# v1.net
KiCad netlist of a schematic drawn in EAGLE
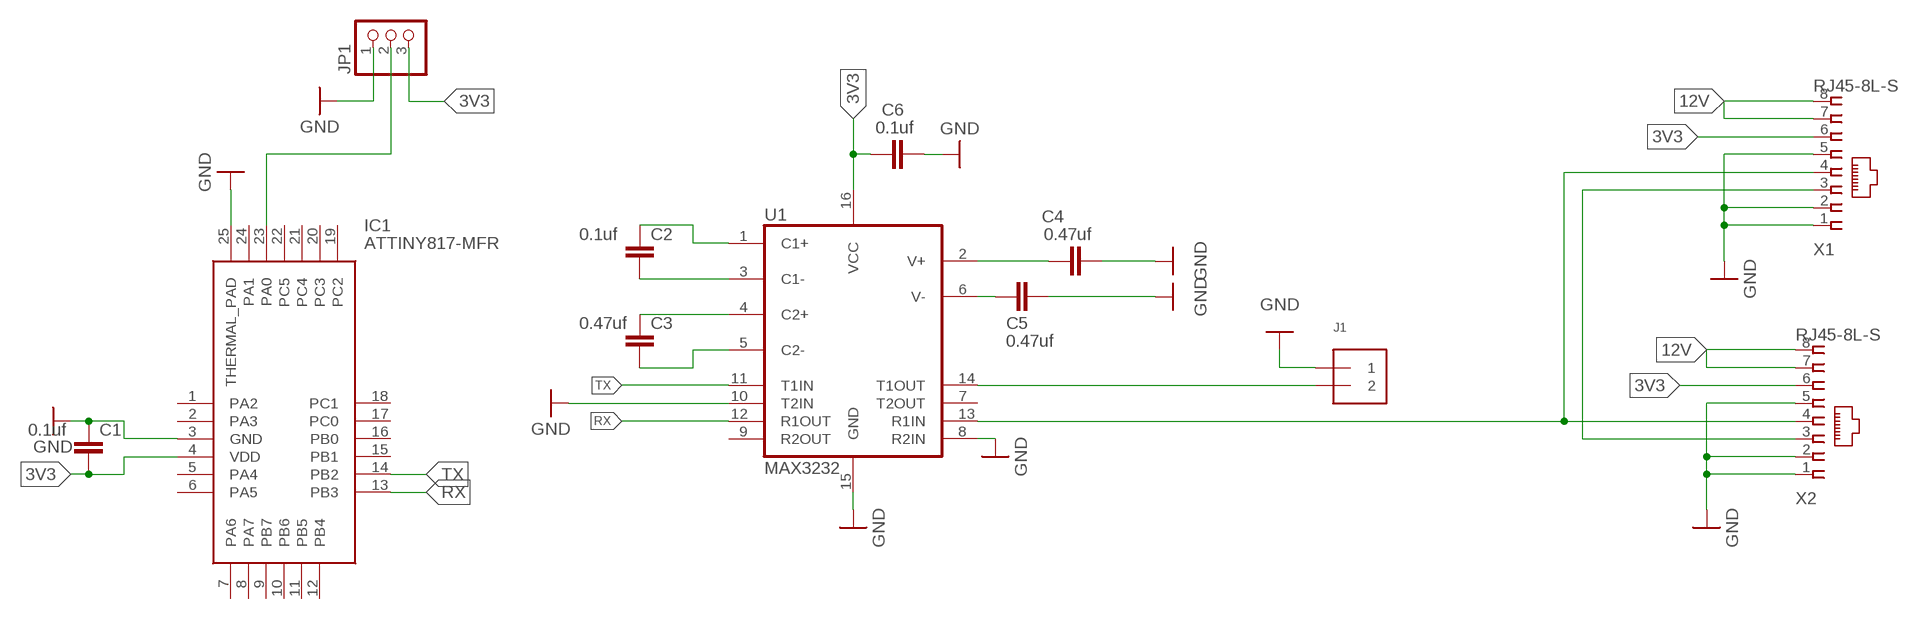
[diagram p0: schematic, sheet 1]

(export (version "E")
  (design (tool "Eeschema 10.0.6"))
  (components
    (comp (ref "C1")
      (value "0.1uf")
      (footprint "eagle-import:C0805")
      (libsource (lib "eagle-import") (part "C-EUC0805"))
    )
    (comp (ref "C2")
      (value "0.1uf")
      (footprint "eagle-import:C0805")
      (libsource (lib "eagle-import") (part "C-EUC0805"))
    )
    (comp (ref "C3")
      (value "0.47uf")
      (footprint "eagle-import:C0805")
      (libsource (lib "eagle-import") (part "C-EUC0805"))
    )
    (comp (ref "C4")
      (value "0.47uf")
      (footprint "eagle-import:C0805")
      (libsource (lib "eagle-import") (part "C-EUC0805"))
    )
    (comp (ref "C5")
      (value "0.47uf")
      (footprint "eagle-import:C0805")
      (libsource (lib "eagle-import") (part "C-EUC0805"))
    )
    (comp (ref "C6")
      (value "0.1uf")
      (footprint "eagle-import:C0805")
      (libsource (lib "eagle-import") (part "C-EUC0805"))
    )
    (comp (ref "IC1")
      (value "ATTINY817-MFR")
      (footprint "eagle-import:QFN50P400X400X90-25N")
      (fields
        (field (name "MOUSER_PART_NUMBER") "579-ATTINY817-MFR")
        (field (name "RS_PART_NUMBER") "1682807P")
      )
      (libsource (lib "eagle-import") (part "ATTINY817-MFR"))
    )
    (comp (ref "J1")
      (value "TERMBLOCK_1X2")
      (footprint "eagle-import:TERMBLOCK_1X2-3.5MM")
      (libsource (lib "eagle-import") (part "TERMBLOCK_1X2"))
    )
    (comp (ref "JP1")
      (value "PINHD-1X3")
      (footprint "eagle-import:1X03")
      (libsource (lib "eagle-import") (part "PINHD-1X3"))
    )
    (comp (ref "U1")
      (value "MAX3232")
      (footprint "eagle-import:SO16")
      (libsource (lib "eagle-import") (part "MAX2323SOIC16"))
    )
    (comp (ref "X1")
      (value "RJ45-8L-S")
      (footprint "eagle-import:RJ45-NO-SHIELD")
      (fields (field (name "MF") "TYCO ELECTRONICS"))
      (libsource (lib "eagle-import") (part "RJ45-8L-S"))
    )
    (comp (ref "X2")
      (value "RJ45-8L-S")
      (footprint "eagle-import:RJ45-NO-SHIELD")
      (fields (field (name "MF") "TYCO ELECTRONICS"))
      (libsource (lib "eagle-import") (part "RJ45-8L-S"))
    )
  )
  (nets
    (net (code "1") (name "3V3") (class "Default")
      (node (ref "C1") (pin "2") (pinfunction "2_2") (pintype "passive"))
      (node (ref "C6") (pin "2") (pinfunction "2_2") (pintype "passive"))
      (node (ref "IC1") (pin "4") (pinfunction "VDD_4") (pintype "bidirectional"))
      (node (ref "JP1") (pin "3") (pinfunction "3_3") (pintype "passive"))
      (node (ref "U1") (pin "16") (pinfunction "VCC_16") (pintype "bidirectional"))
      (node (ref "X1") (pin "6") (pinfunction "6_6") (pintype "passive"))
      (node (ref "X2") (pin "6") (pinfunction "6_6") (pintype "passive"))
    )
    (net (code "2") (name "12V") (class "Default")
      (node (ref "X1") (pin "7") (pinfunction "7_7") (pintype "passive"))
      (node (ref "X1") (pin "8") (pinfunction "8_8") (pintype "passive"))
      (node (ref "X2") (pin "7") (pinfunction "7_7") (pintype "passive"))
      (node (ref "X2") (pin "8") (pinfunction "8_8") (pintype "passive"))
    )
    (net (code "3") (name "GND") (class "Default")
      (node (ref "C1") (pin "1") (pinfunction "1_1") (pintype "passive"))
      (node (ref "C4") (pin "1") (pinfunction "1_1") (pintype "passive"))
      (node (ref "C5") (pin "1") (pinfunction "1_1") (pintype "passive"))
      (node (ref "C6") (pin "1") (pinfunction "1_1") (pintype "passive"))
      (node (ref "IC1") (pin "25") (pinfunction "THERMAL_PAD_25") (pintype "bidirectional"))
      (node (ref "IC1") (pin "3") (pinfunction "GND_3") (pintype "bidirectional"))
      (node (ref "J1") (pin "1") (pinfunction "1_1") (pintype "passive"))
      (node (ref "JP1") (pin "1") (pinfunction "1_1") (pintype "passive"))
      (node (ref "U1") (pin "10") (pinfunction "T2IN_10") (pintype "input"))
      (node (ref "U1") (pin "15") (pinfunction "GND_15") (pintype "bidirectional"))
      (node (ref "U1") (pin "8") (pinfunction "R2IN_8") (pintype "input"))
      (node (ref "X1") (pin "1") (pinfunction "1_1") (pintype "passive"))
      (node (ref "X1") (pin "2") (pinfunction "2_2") (pintype "passive"))
      (node (ref "X1") (pin "5") (pinfunction "5_5") (pintype "passive"))
      (node (ref "X2") (pin "1") (pinfunction "1_1") (pintype "passive"))
      (node (ref "X2") (pin "2") (pinfunction "2_2") (pintype "passive"))
      (node (ref "X2") (pin "5") (pinfunction "5_5") (pintype "passive"))
    )
    (net (code "4") (name "Net-(IC1-PA0)") (class "Default")
      (node (ref "IC1") (pin "23") (pinfunction "PA0_23") (pintype "bidirectional"))
      (node (ref "JP1") (pin "2") (pinfunction "2_2") (pintype "passive"))
    )
    (net (code "5") (name "Net-(U1-C1+)") (class "Default")
      (node (ref "C2") (pin "1") (pinfunction "1_1") (pintype "passive"))
      (node (ref "U1") (pin "1") (pinfunction "C1+_1") (pintype "bidirectional"))
    )
    (net (code "6") (name "Net-(U1-C1-)") (class "Default")
      (node (ref "C2") (pin "2") (pinfunction "2_2") (pintype "passive"))
      (node (ref "U1") (pin "3") (pinfunction "C1-_3") (pintype "bidirectional"))
    )
    (net (code "7") (name "Net-(U1-C2+)") (class "Default")
      (node (ref "C3") (pin "1") (pinfunction "1_1") (pintype "passive"))
      (node (ref "U1") (pin "4") (pinfunction "C2+_4") (pintype "bidirectional"))
    )
    (net (code "8") (name "Net-(U1-C2-)") (class "Default")
      (node (ref "C3") (pin "2") (pinfunction "2_2") (pintype "passive"))
      (node (ref "U1") (pin "5") (pinfunction "C2-_5") (pintype "bidirectional"))
    )
    (net (code "9") (name "Net-(U1-R1IN)") (class "Default")
      (node (ref "U1") (pin "13") (pinfunction "R1IN_13") (pintype "input"))
      (node (ref "X1") (pin "4") (pinfunction "4_4") (pintype "passive"))
      (node (ref "X2") (pin "4") (pinfunction "4_4") (pintype "passive"))
    )
    (net (code "10") (name "Net-(U1-T1OUT)") (class "Default")
      (node (ref "J1") (pin "2") (pinfunction "2_2") (pintype "passive"))
      (node (ref "U1") (pin "14") (pinfunction "T1OUT_14") (pintype "output"))
    )
    (net (code "11") (name "Net-(U1-V+)") (class "Default")
      (node (ref "C4") (pin "2") (pinfunction "2_2") (pintype "passive"))
      (node (ref "U1") (pin "2") (pinfunction "V+_2") (pintype "bidirectional"))
    )
    (net (code "12") (name "Net-(U1-V-)") (class "Default")
      (node (ref "C5") (pin "2") (pinfunction "2_2") (pintype "passive"))
      (node (ref "U1") (pin "6") (pinfunction "V-_6") (pintype "bidirectional"))
    )
    (net (code "13") (name "Net-(X1-Pad3)") (class "Default")
      (node (ref "X1") (pin "3") (pinfunction "3_3") (pintype "passive"))
      (node (ref "X2") (pin "3") (pinfunction "3_3") (pintype "passive"))
    )
    (net (code "14") (name "RX") (class "Default")
      (node (ref "IC1") (pin "13") (pinfunction "PB3_13") (pintype "bidirectional"))
      (node (ref "U1") (pin "12") (pinfunction "R1OUT_12") (pintype "output"))
    )
    (net (code "15") (name "TX") (class "Default")
      (node (ref "IC1") (pin "14") (pinfunction "PB2_14") (pintype "bidirectional"))
      (node (ref "U1") (pin "11") (pinfunction "T1IN_11") (pintype "input"))
    )
    (net (code "16") (name "unconnected-(IC1-PA1-Pad24)") (class "Default")
      (node (ref "IC1") (pin "24") (pinfunction "PA1_24") (pintype "bidirectional"))
    )
    (net (code "17") (name "unconnected-(IC1-PA2-Pad1)") (class "Default")
      (node (ref "IC1") (pin "1") (pinfunction "PA2_1") (pintype "bidirectional"))
    )
    (net (code "18") (name "unconnected-(IC1-PA3-Pad2)") (class "Default")
      (node (ref "IC1") (pin "2") (pinfunction "PA3_2") (pintype "bidirectional"))
    )
    (net (code "19") (name "unconnected-(IC1-PA4-Pad5)") (class "Default")
      (node (ref "IC1") (pin "5") (pinfunction "PA4_5") (pintype "bidirectional"))
    )
    (net (code "20") (name "unconnected-(IC1-PA5-Pad6)") (class "Default")
      (node (ref "IC1") (pin "6") (pinfunction "PA5_6") (pintype "bidirectional"))
    )
    (net (code "21") (name "unconnected-(IC1-PA6-Pad7)") (class "Default")
      (node (ref "IC1") (pin "7") (pinfunction "PA6_7") (pintype "bidirectional"))
    )
    (net (code "22") (name "unconnected-(IC1-PA7-Pad8)") (class "Default")
      (node (ref "IC1") (pin "8") (pinfunction "PA7_8") (pintype "bidirectional"))
    )
    (net (code "23") (name "unconnected-(IC1-PB0-Pad16)") (class "Default")
      (node (ref "IC1") (pin "16") (pinfunction "PB0_16") (pintype "bidirectional"))
    )
    (net (code "24") (name "unconnected-(IC1-PB1-Pad15)") (class "Default")
      (node (ref "IC1") (pin "15") (pinfunction "PB1_15") (pintype "bidirectional"))
    )
    (net (code "25") (name "unconnected-(IC1-PB4-Pad12)") (class "Default")
      (node (ref "IC1") (pin "12") (pinfunction "PB4_12") (pintype "bidirectional"))
    )
    (net (code "26") (name "unconnected-(IC1-PB5-Pad11)") (class "Default")
      (node (ref "IC1") (pin "11") (pinfunction "PB5_11") (pintype "bidirectional"))
    )
    (net (code "27") (name "unconnected-(IC1-PB6-Pad10)") (class "Default")
      (node (ref "IC1") (pin "10") (pinfunction "PB6_10") (pintype "bidirectional"))
    )
    (net (code "28") (name "unconnected-(IC1-PB7-Pad9)") (class "Default")
      (node (ref "IC1") (pin "9") (pinfunction "PB7_9") (pintype "bidirectional"))
    )
    (net (code "29") (name "unconnected-(IC1-PC0-Pad17)") (class "Default")
      (node (ref "IC1") (pin "17") (pinfunction "PC0_17") (pintype "bidirectional"))
    )
    (net (code "30") (name "unconnected-(IC1-PC1-Pad18)") (class "Default")
      (node (ref "IC1") (pin "18") (pinfunction "PC1_18") (pintype "bidirectional"))
    )
    (net (code "31") (name "unconnected-(IC1-PC2-Pad19)") (class "Default")
      (node (ref "IC1") (pin "19") (pinfunction "PC2_19") (pintype "bidirectional"))
    )
    (net (code "32") (name "unconnected-(IC1-PC3-Pad20)") (class "Default")
      (node (ref "IC1") (pin "20") (pinfunction "PC3_20") (pintype "bidirectional"))
    )
    (net (code "33") (name "unconnected-(IC1-PC4-Pad21)") (class "Default")
      (node (ref "IC1") (pin "21") (pinfunction "PC4_21") (pintype "bidirectional"))
    )
    (net (code "34") (name "unconnected-(IC1-PC5-Pad22)") (class "Default")
      (node (ref "IC1") (pin "22") (pinfunction "PC5_22") (pintype "bidirectional"))
    )
    (net (code "35") (name "unconnected-(U1-R2OUT-Pad9)") (class "Default")
      (node (ref "U1") (pin "9") (pinfunction "R2OUT_9") (pintype "output"))
    )
    (net (code "36") (name "unconnected-(U1-T2OUT-Pad7)") (class "Default")
      (node (ref "U1") (pin "7") (pinfunction "T2OUT_7") (pintype "output"))
    )
  )
)
